# design.net
KiCad netlist of a schematic drawn in Altium Designer
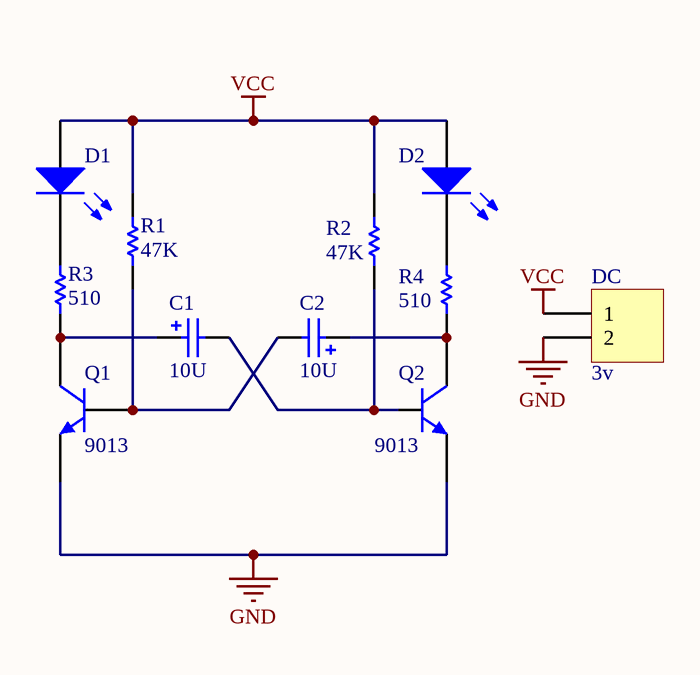
[diagram p0: 原理图.SchDoc]

(export (version "E")
  (design (tool "Eeschema 10.0.6"))
  (components
    (comp (ref "C1")
      (value "10U")
      (footprint "CAPPR2-5x6.8")
      (description "Polarized Capacitor (Axial)")
      (fields (field (name "PUBLISHER") "Altium Limited"))
      (libsource (lib "Miscellaneous Devices") (part "Cap Pol2"))
    )
    (comp (ref "C2")
      (value "10U")
      (footprint "CAPPR2-5x6.8")
      (description "Polarized Capacitor (Axial)")
      (fields (field (name "PUBLISHER") "Altium Limited"))
      (libsource (lib "Miscellaneous Devices") (part "Cap Pol2"))
    )
    (comp (ref "D1")
      (value "LED0")
      (footprint "CAPPR2-5x6.8")
      (description "Typical INFRARED GaAs LED")
      (fields (field (name "PUBLISHER") "Altium Limited"))
      (libsource (lib "Miscellaneous Devices") (part "LED0"))
    )
    (comp (ref "D2")
      (value "LED0")
      (footprint "CAPPR2-5x6.8")
      (description "Typical INFRARED GaAs LED")
      (fields (field (name "PUBLISHER") "Altium Limited"))
      (libsource (lib "Miscellaneous Devices") (part "LED0"))
    )
    (comp (ref "DC")
      (value "3v")
      (footprint "HDR1X2")
      (description "Header, 2-Pin")
      (fields (field (name "PUBLISHER") "Altium Limited"))
      (libsource (lib "Miscellaneous Connectors") (part "Header 2"))
    )
    (comp (ref "Q1")
      (value "9013")
      (footprint "BCY-W3/E4")
      (description "NPN General Purpose Amplifier")
      (fields (field (name "PUBLISHER") "Altium Limited"))
      (libsource (lib "Miscellaneous Devices") (part "2N3904"))
    )
    (comp (ref "Q2")
      (value "9013")
      (footprint "BCY-W3/E4")
      (description "NPN General Purpose Amplifier")
      (fields (field (name "PUBLISHER") "Altium Limited"))
      (libsource (lib "Miscellaneous Devices") (part "2N3904"))
    )
    (comp (ref "R1")
      (value "47K")
      (footprint "AXIAL-0.3")
      (description "Resistor")
      (fields (field (name "PUBLISHER") "Altium Limited"))
      (libsource (lib "Miscellaneous Devices") (part "Res1"))
    )
    (comp (ref "R2")
      (value "47K")
      (footprint "AXIAL-0.3")
      (description "Resistor")
      (fields (field (name "PUBLISHER") "Altium Limited"))
      (libsource (lib "Miscellaneous Devices") (part "Res1"))
    )
    (comp (ref "R3")
      (value "510")
      (footprint "AXIAL-0.3")
      (description "Resistor")
      (fields (field (name "PUBLISHER") "Altium Limited"))
      (libsource (lib "Miscellaneous Devices") (part "Res1"))
    )
    (comp (ref "R4")
      (value "510")
      (footprint "AXIAL-0.3")
      (description "Resistor")
      (fields (field (name "PUBLISHER") "Altium Limited"))
      (libsource (lib "Miscellaneous Devices") (part "Res1"))
    )
  )
  (nets
    (net (code "1") (name "GND") (class "Default")
      (node (ref "DC") (pin "2") (pinfunction "2_2") (pintype "passive"))
      (node (ref "Q1") (pin "1") (pinfunction "E_1") (pintype "passive"))
      (node (ref "Q2") (pin "1") (pinfunction "E_1") (pintype "passive"))
    )
    (net (code "2") (name "Net-(D1-K)") (class "Default")
      (node (ref "D1") (pin "2") (pinfunction "K_2") (pintype "passive"))
      (node (ref "R3") (pin "2") (pinfunction "2_2") (pintype "passive"))
    )
    (net (code "3") (name "Net-(D2-K)") (class "Default")
      (node (ref "D2") (pin "2") (pinfunction "K_2") (pintype "passive"))
      (node (ref "R4") (pin "2") (pinfunction "2_2") (pintype "passive"))
    )
    (net (code "4") (name "Net-(Q1-B)") (class "Default")
      (node (ref "C2") (pin "2") (pinfunction "2_2") (pintype "passive"))
      (node (ref "Q1") (pin "2") (pinfunction "B_2") (pintype "passive"))
      (node (ref "R1") (pin "1") (pinfunction "1_1") (pintype "passive"))
    )
    (net (code "5") (name "Net-(Q1-C)") (class "Default")
      (node (ref "C1") (pin "1") (pinfunction "1_1") (pintype "passive"))
      (node (ref "Q1") (pin "3") (pinfunction "C_3") (pintype "passive"))
      (node (ref "R3") (pin "1") (pinfunction "1_1") (pintype "passive"))
    )
    (net (code "6") (name "Net-(Q2-B)") (class "Default")
      (node (ref "C1") (pin "2") (pinfunction "2_2") (pintype "passive"))
      (node (ref "Q2") (pin "2") (pinfunction "B_2") (pintype "passive"))
      (node (ref "R2") (pin "1") (pinfunction "1_1") (pintype "passive"))
    )
    (net (code "7") (name "Net-(Q2-C)") (class "Default")
      (node (ref "C2") (pin "1") (pinfunction "1_1") (pintype "passive"))
      (node (ref "Q2") (pin "3") (pinfunction "C_3") (pintype "passive"))
      (node (ref "R4") (pin "1") (pinfunction "1_1") (pintype "passive"))
    )
    (net (code "8") (name "VCC") (class "Default")
      (node (ref "D1") (pin "1") (pinfunction "A_1") (pintype "passive"))
      (node (ref "D2") (pin "1") (pinfunction "A_1") (pintype "passive"))
      (node (ref "DC") (pin "1") (pinfunction "1_1") (pintype "passive"))
      (node (ref "R1") (pin "2") (pinfunction "2_2") (pintype "passive"))
      (node (ref "R2") (pin "2") (pinfunction "2_2") (pintype "passive"))
    )
  )
)
